# CMoy-Pro-Buffer-Board-V_1_0_0_1a.net
KiCad netlist of a schematic drawn in EAGLE
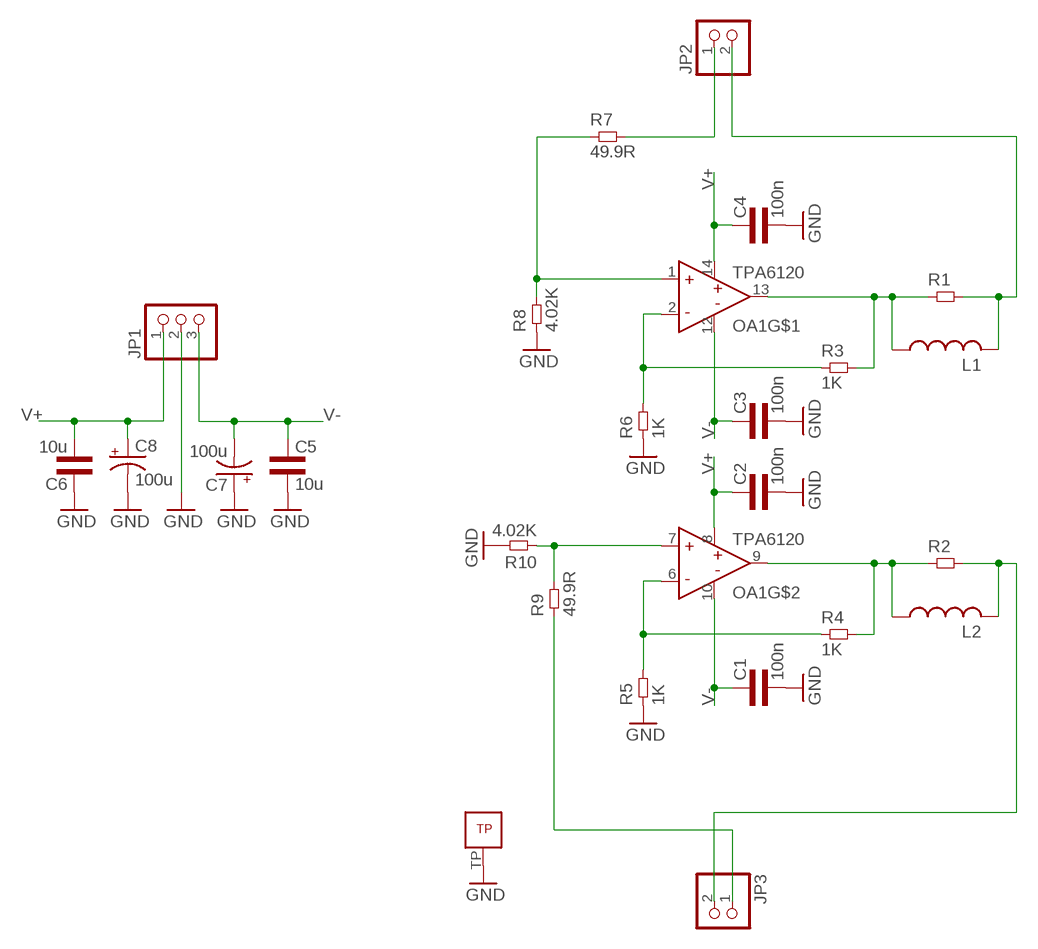
[diagram p0: schematic, sheet 1]

(export (version "E")
  (design (tool "Eeschema 10.0.6"))
  (components
    (comp (ref "C1")
      (value "100n")
      (footprint "eagle-import:0603L3")
      (libsource (lib "eagle-import") (part "CAP0603L3"))
    )
    (comp (ref "C2")
      (value "100n")
      (footprint "eagle-import:0603L3")
      (libsource (lib "eagle-import") (part "CAP0603L3"))
    )
    (comp (ref "C3")
      (value "100n")
      (footprint "eagle-import:0603L3")
      (libsource (lib "eagle-import") (part "CAP0603L3"))
    )
    (comp (ref "C4")
      (value "100n")
      (footprint "eagle-import:0603L3")
      (libsource (lib "eagle-import") (part "CAP0603L3"))
    )
    (comp (ref "C5")
      (value "10u")
      (footprint "eagle-import:0805L3")
      (libsource (lib "eagle-import") (part "CAP0805L3"))
    )
    (comp (ref "C6")
      (value "10u")
      (footprint "eagle-import:0805L3")
      (libsource (lib "eagle-import") (part "CAP0805L3"))
    )
    (comp (ref "C7")
      (value "100u")
      (footprint "eagle-import:CT7343")
      (libsource (lib "eagle-import") (part "CPOL-USCT7343"))
    )
    (comp (ref "C8")
      (value "100u")
      (footprint "eagle-import:CT7343")
      (libsource (lib "eagle-import") (part "CPOL-USCT7343"))
    )
    (comp (ref "JP1")
      (value "PINHD-1X3")
      (footprint "eagle-import:1X03")
      (libsource (lib "eagle-import") (part "PINHD-1X3"))
    )
    (comp (ref "JP2")
      (value "PINHD-1X2")
      (footprint "eagle-import:1X02")
      (libsource (lib "eagle-import") (part "PINHD-1X2"))
    )
    (comp (ref "JP3")
      (value "PINHD-1X2")
      (footprint "eagle-import:1X02")
      (libsource (lib "eagle-import") (part "PINHD-1X2"))
    )
    (comp (ref "L1")
      (value "L-USL2012C")
      (footprint "eagle-import:L2012C")
      (libsource (lib "eagle-import") (part "L-USL2012C"))
    )
    (comp (ref "L2")
      (value "L-USL2012C")
      (footprint "eagle-import:L2012C")
      (libsource (lib "eagle-import") (part "L-USL2012C"))
    )
    (comp (ref "OA1")
      (value "TPA6120QFN")
      (footprint "eagle-import:S-PVQFN-N14")
      (libsource (lib "eagle-import") (part "TPA6120QFN"))
    )
    (comp (ref "R1")
      (value "RES1210L3")
      (footprint "eagle-import:1210L3")
      (libsource (lib "eagle-import") (part "RES1210L3"))
    )
    (comp (ref "R2")
      (value "RES1210L3")
      (footprint "eagle-import:1210L3")
      (libsource (lib "eagle-import") (part "RES1210L3"))
    )
    (comp (ref "R3")
      (value "1K")
      (footprint "eagle-import:0603L3")
      (libsource (lib "eagle-import") (part "RES0603L3"))
    )
    (comp (ref "R4")
      (value "1K")
      (footprint "eagle-import:0603L3")
      (libsource (lib "eagle-import") (part "RES0603L3"))
    )
    (comp (ref "R5")
      (value "1K")
      (footprint "eagle-import:0603L3")
      (libsource (lib "eagle-import") (part "RES0603L3"))
    )
    (comp (ref "R6")
      (value "1K")
      (footprint "eagle-import:0603L3")
      (libsource (lib "eagle-import") (part "RES0603L3"))
    )
    (comp (ref "R7")
      (value "49.9R")
      (footprint "eagle-import:0603L3")
      (libsource (lib "eagle-import") (part "RES0603L3"))
    )
    (comp (ref "R8")
      (value "4.02K")
      (footprint "eagle-import:0603L3")
      (libsource (lib "eagle-import") (part "RES0603L3"))
    )
    (comp (ref "R9")
      (value "49.9R")
      (footprint "eagle-import:0603L3")
      (libsource (lib "eagle-import") (part "RES0603L3"))
    )
    (comp (ref "R10")
      (value "4.02K")
      (footprint "eagle-import:0603L3")
      (libsource (lib "eagle-import") (part "RES0603L3"))
    )
  )
  (nets
    (net (code "1") (name "/V+") (class "Default")
      (node (ref "C2") (pin "P$1") (pinfunction "1_P$1") (pintype "bidirectional"))
      (node (ref "C4") (pin "P$1") (pinfunction "1_P$1") (pintype "bidirectional"))
      (node (ref "C6") (pin "2") (pinfunction "2_2") (pintype "bidirectional"))
      (node (ref "C8") (pin "+") (pinfunction "+_+") (pintype "passive"))
      (node (ref "JP1") (pin "1") (pinfunction "1_1") (pintype "passive"))
      (node (ref "OA1") (pin "14") (pinfunction "V+_14") (pintype "bidirectional"))
      (node (ref "OA1") (pin "8") (pinfunction "V+_8") (pintype "bidirectional"))
    )
    (net (code "2") (name "/V-") (class "Default")
      (node (ref "C1") (pin "P$1") (pinfunction "1_P$1") (pintype "bidirectional"))
      (node (ref "C3") (pin "P$1") (pinfunction "1_P$1") (pintype "bidirectional"))
      (node (ref "C5") (pin "1") (pinfunction "1_1") (pintype "bidirectional"))
      (node (ref "C7") (pin "-") (pinfunction "-_-") (pintype "passive"))
      (node (ref "JP1") (pin "3") (pinfunction "3_3") (pintype "passive"))
      (node (ref "OA1") (pin "10") (pinfunction "V-_10") (pintype "bidirectional"))
      (node (ref "OA1") (pin "12") (pinfunction "V-_12") (pintype "bidirectional"))
    )
    (net (code "3") (name "GND") (class "Default")
      (node (ref "C1") (pin "P$2") (pinfunction "2_P$2") (pintype "bidirectional"))
      (node (ref "C2") (pin "P$2") (pinfunction "2_P$2") (pintype "bidirectional"))
      (node (ref "C3") (pin "P$2") (pinfunction "2_P$2") (pintype "bidirectional"))
      (node (ref "C4") (pin "P$2") (pinfunction "2_P$2") (pintype "bidirectional"))
      (node (ref "C5") (pin "2") (pinfunction "2_2") (pintype "bidirectional"))
      (node (ref "C6") (pin "1") (pinfunction "1_1") (pintype "bidirectional"))
      (node (ref "C7") (pin "+") (pinfunction "+_+") (pintype "passive"))
      (node (ref "C8") (pin "-") (pinfunction "-_-") (pintype "passive"))
      (node (ref "JP1") (pin "2") (pinfunction "2_2") (pintype "passive"))
      (node (ref "OA1") (pin "TP") (pinfunction "TP_TP") (pintype "bidirectional"))
      (node (ref "R10") (pin "P$2") (pinfunction "2_P$2") (pintype "bidirectional"))
      (node (ref "R5") (pin "P$1") (pinfunction "1_P$1") (pintype "bidirectional"))
      (node (ref "R6") (pin "P$1") (pinfunction "1_P$1") (pintype "bidirectional"))
      (node (ref "R8") (pin "P$1") (pinfunction "1_P$1") (pintype "bidirectional"))
    )
    (net (code "4") (name "Net-(OA1A-IN+)") (class "Default")
      (node (ref "OA1") (pin "1") (pinfunction "IN+_1") (pintype "bidirectional"))
      (node (ref "R7") (pin "P$1") (pinfunction "1_P$1") (pintype "bidirectional"))
      (node (ref "R8") (pin "P$2") (pinfunction "2_P$2") (pintype "bidirectional"))
    )
    (net (code "5") (name "Net-(OA1A-IN-)") (class "Default")
      (node (ref "OA1") (pin "2") (pinfunction "IN-_2") (pintype "bidirectional"))
      (node (ref "R3") (pin "P$1") (pinfunction "1_P$1") (pintype "bidirectional"))
      (node (ref "R6") (pin "P$2") (pinfunction "2_P$2") (pintype "bidirectional"))
    )
    (net (code "6") (name "Net-(OA1A-OUT)") (class "Default")
      (node (ref "L1") (pin "1") (pinfunction "1_1") (pintype "passive"))
      (node (ref "OA1") (pin "13") (pinfunction "OUT_13") (pintype "bidirectional"))
      (node (ref "R1") (pin "P$1") (pinfunction "1_P$1") (pintype "bidirectional"))
      (node (ref "R3") (pin "P$2") (pinfunction "2_P$2") (pintype "bidirectional"))
    )
    (net (code "7") (name "Net-(OA1B-IN+)") (class "Default")
      (node (ref "OA1") (pin "7") (pinfunction "IN+_7") (pintype "bidirectional"))
      (node (ref "R10") (pin "P$1") (pinfunction "1_P$1") (pintype "bidirectional"))
      (node (ref "R9") (pin "P$2") (pinfunction "2_P$2") (pintype "bidirectional"))
    )
    (net (code "8") (name "Net-(OA1B-IN-)") (class "Default")
      (node (ref "OA1") (pin "6") (pinfunction "IN-_6") (pintype "bidirectional"))
      (node (ref "R4") (pin "P$1") (pinfunction "1_P$1") (pintype "bidirectional"))
      (node (ref "R5") (pin "P$2") (pinfunction "2_P$2") (pintype "bidirectional"))
    )
    (net (code "9") (name "Net-(OA1B-OUT)") (class "Default")
      (node (ref "L2") (pin "1") (pinfunction "1_1") (pintype "passive"))
      (node (ref "OA1") (pin "9") (pinfunction "OUT_9") (pintype "bidirectional"))
      (node (ref "R2") (pin "P$1") (pinfunction "1_P$1") (pintype "bidirectional"))
      (node (ref "R4") (pin "P$2") (pinfunction "2_P$2") (pintype "bidirectional"))
    )
    (net (code "10") (name "Net-(R1-2)") (class "Default")
      (node (ref "JP2") (pin "2") (pinfunction "2_2") (pintype "passive"))
      (node (ref "L1") (pin "2") (pinfunction "2_2") (pintype "passive"))
      (node (ref "R1") (pin "P$2") (pinfunction "2_P$2") (pintype "bidirectional"))
    )
    (net (code "11") (name "Net-(R2-2)") (class "Default")
      (node (ref "JP3") (pin "2") (pinfunction "2_2") (pintype "passive"))
      (node (ref "L2") (pin "2") (pinfunction "2_2") (pintype "passive"))
      (node (ref "R2") (pin "P$2") (pinfunction "2_P$2") (pintype "bidirectional"))
    )
    (net (code "12") (name "Net-(R7-2)") (class "Default")
      (node (ref "JP2") (pin "1") (pinfunction "1_1") (pintype "passive"))
      (node (ref "R7") (pin "P$2") (pinfunction "2_P$2") (pintype "bidirectional"))
    )
    (net (code "13") (name "Net-(R9-1)") (class "Default")
      (node (ref "JP3") (pin "1") (pinfunction "1_1") (pintype "passive"))
      (node (ref "R9") (pin "P$1") (pinfunction "1_P$1") (pintype "bidirectional"))
    )
  )
)
